# FlashMob.net
KiCad netlist of a schematic drawn in EAGLE
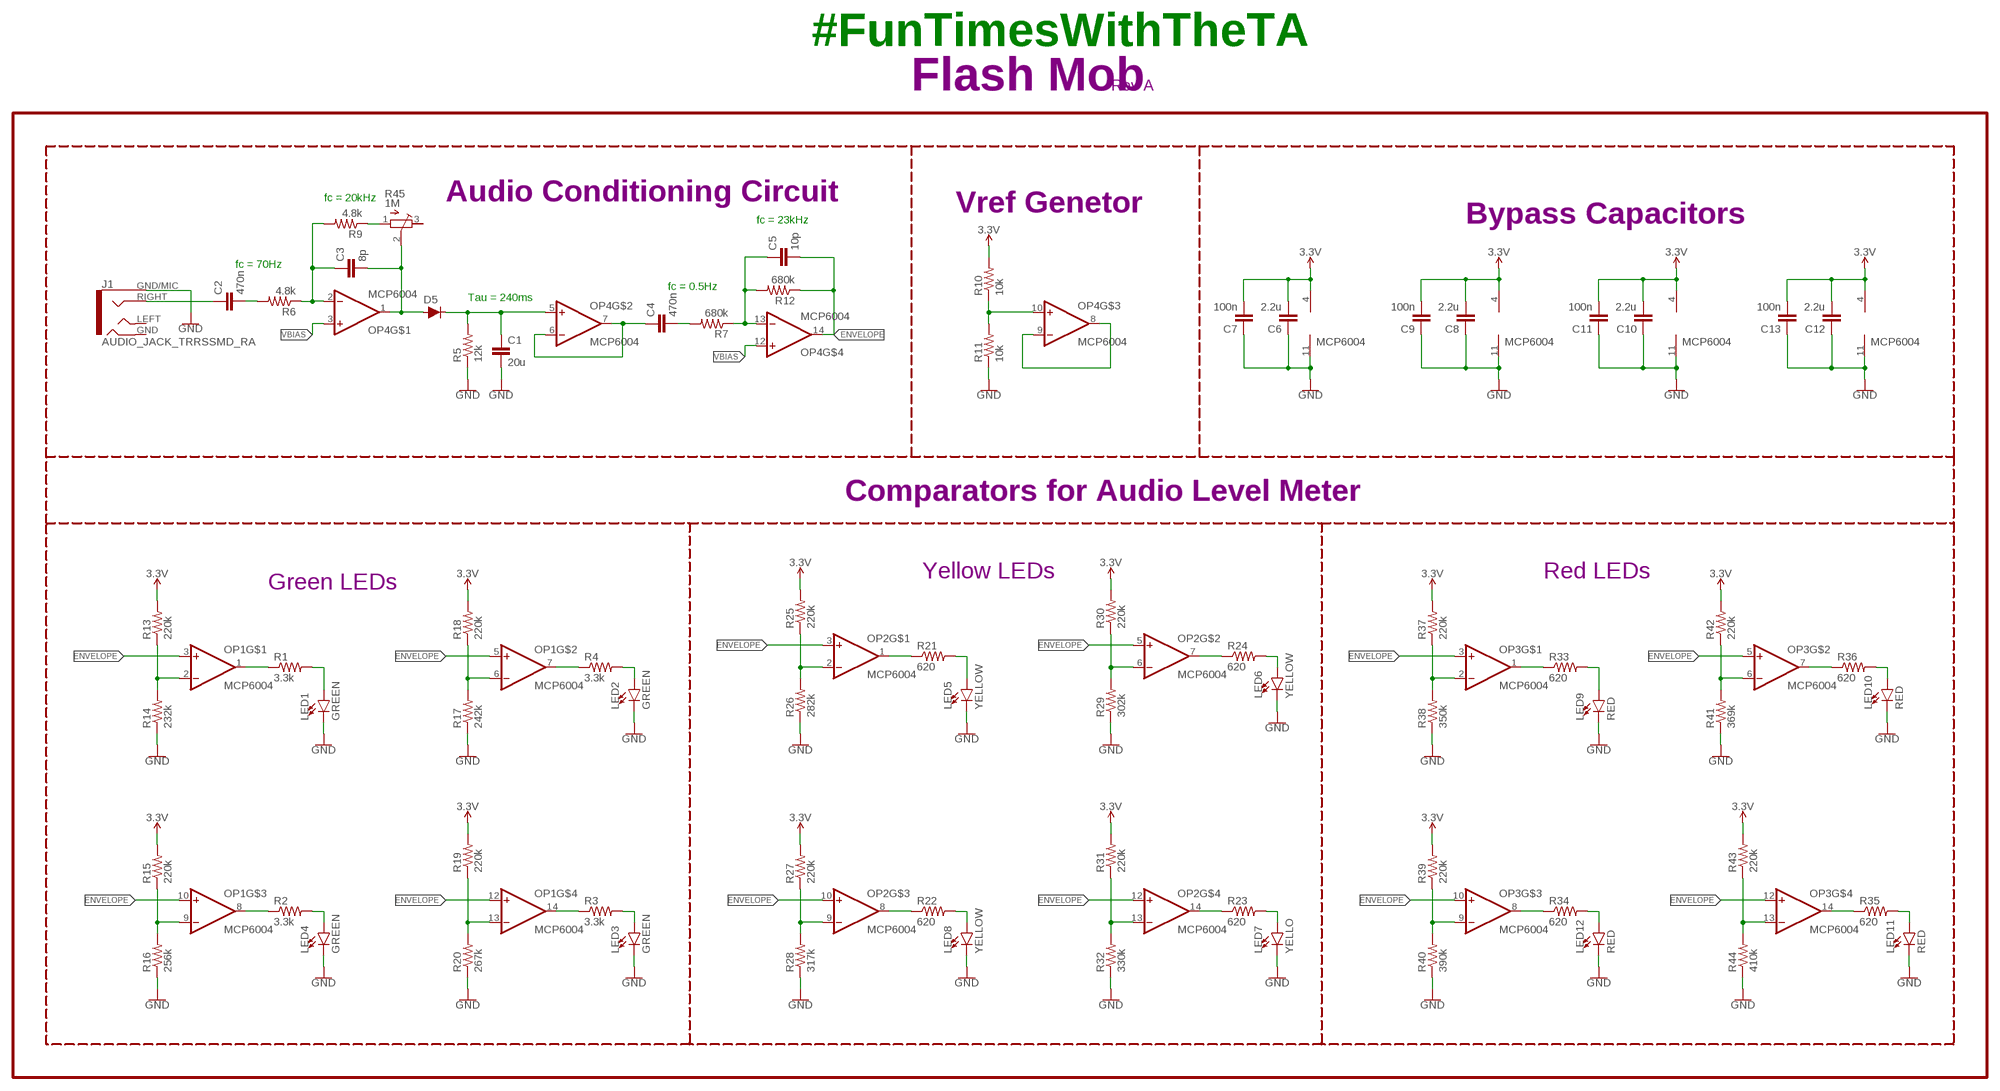
[diagram p0: schematic, sheet 1]

(export (version "E")
  (design (tool "Eeschema 10.0.6"))
  (components
    (comp (ref "C1")
      (value "20u")
      (footprint "eagle-import:C0402")
      (libsource (lib "eagle-import") (part "CAPACITOR0402"))
    )
    (comp (ref "C2")
      (value "470n")
      (footprint "eagle-import:C0402")
      (libsource (lib "eagle-import") (part "CAPACITOR0402"))
    )
    (comp (ref "C3")
      (value "8p")
      (footprint "eagle-import:C0402")
      (libsource (lib "eagle-import") (part "CAPACITOR0402"))
    )
    (comp (ref "C4")
      (value "470n")
      (footprint "eagle-import:C0402")
      (libsource (lib "eagle-import") (part "CAPACITOR0402"))
    )
    (comp (ref "C5")
      (value "10p")
      (footprint "eagle-import:C0402")
      (libsource (lib "eagle-import") (part "CAPACITOR0402"))
    )
    (comp (ref "C6")
      (value "2.2u")
      (footprint "eagle-import:C0402")
      (libsource (lib "eagle-import") (part "CAPACITOR0402"))
    )
    (comp (ref "C7")
      (value "100n")
      (footprint "eagle-import:C0402")
      (libsource (lib "eagle-import") (part "CAPACITOR0402"))
    )
    (comp (ref "C8")
      (value "2.2u")
      (footprint "eagle-import:C0402")
      (libsource (lib "eagle-import") (part "CAPACITOR0402"))
    )
    (comp (ref "C9")
      (value "100n")
      (footprint "eagle-import:C0402")
      (libsource (lib "eagle-import") (part "CAPACITOR0402"))
    )
    (comp (ref "C10")
      (value "2.2u")
      (footprint "eagle-import:C0402")
      (libsource (lib "eagle-import") (part "CAPACITOR0402"))
    )
    (comp (ref "C11")
      (value "100n")
      (footprint "eagle-import:C0402")
      (libsource (lib "eagle-import") (part "CAPACITOR0402"))
    )
    (comp (ref "C12")
      (value "2.2u")
      (footprint "eagle-import:C0402")
      (libsource (lib "eagle-import") (part "CAPACITOR0402"))
    )
    (comp (ref "C13")
      (value "100n")
      (footprint "eagle-import:C0402")
      (libsource (lib "eagle-import") (part "CAPACITOR0402"))
    )
    (comp (ref "D5")
      (value "DIODE-BAS16J")
      (footprint "eagle-import:SOD-323")
      (libsource (lib "eagle-import") (part "DIODE-BAS16J"))
    )
    (comp (ref "J1")
      (value "AUDIO_JACK_TRRSSMD_RA")
      (footprint "eagle-import:AUDIO_JACK_3.5MM_TRRS_SMD_RA")
      (libsource (lib "eagle-import") (part "AUDIO_JACK_TRRSSMD_RA"))
    )
    (comp (ref "LED1")
      (value "GREEN")
      (footprint "eagle-import:LED-0603")
      (libsource (lib "eagle-import") (part "LED0603"))
    )
    (comp (ref "LED2")
      (value "GREEN")
      (footprint "eagle-import:LED-0603")
      (libsource (lib "eagle-import") (part "LED0603"))
    )
    (comp (ref "LED3")
      (value "GREEN")
      (footprint "eagle-import:LED-0603")
      (libsource (lib "eagle-import") (part "LED0603"))
    )
    (comp (ref "LED4")
      (value "GREEN")
      (footprint "eagle-import:LED-0603")
      (libsource (lib "eagle-import") (part "LED0603"))
    )
    (comp (ref "LED5")
      (value "YELLOW")
      (footprint "eagle-import:LED-0603")
      (libsource (lib "eagle-import") (part "LED0603"))
    )
    (comp (ref "LED6")
      (value "YELLOW")
      (footprint "eagle-import:LED-0603")
      (libsource (lib "eagle-import") (part "LED0603"))
    )
    (comp (ref "LED7")
      (value "YELLO")
      (footprint "eagle-import:LED-0603")
      (libsource (lib "eagle-import") (part "LED0603"))
    )
    (comp (ref "LED8")
      (value "YELLOW")
      (footprint "eagle-import:LED-0603")
      (libsource (lib "eagle-import") (part "LED0603"))
    )
    (comp (ref "LED9")
      (value "RED")
      (footprint "eagle-import:LED-0603")
      (libsource (lib "eagle-import") (part "LED0603"))
    )
    (comp (ref "LED10")
      (value "RED")
      (footprint "eagle-import:LED-0603")
      (libsource (lib "eagle-import") (part "LED0603"))
    )
    (comp (ref "LED11")
      (value "RED")
      (footprint "eagle-import:LED-0603")
      (libsource (lib "eagle-import") (part "LED0603"))
    )
    (comp (ref "LED12")
      (value "RED")
      (footprint "eagle-import:LED-0603")
      (libsource (lib "eagle-import") (part "LED0603"))
    )
    (comp (ref "OP1")
      (value "MCP6004")
      (footprint "eagle-import:TSSOP14")
      (libsource (lib "eagle-import") (part "OP-QUAD-TSSOP14"))
    )
    (comp (ref "OP2")
      (value "MCP6004")
      (footprint "eagle-import:TSSOP14")
      (libsource (lib "eagle-import") (part "OP-QUAD-TSSOP14"))
    )
    (comp (ref "OP3")
      (value "MCP6004")
      (footprint "eagle-import:TSSOP14")
      (libsource (lib "eagle-import") (part "OP-QUAD-TSSOP14"))
    )
    (comp (ref "OP4")
      (value "MCP6004")
      (footprint "eagle-import:TSSOP14")
      (libsource (lib "eagle-import") (part "OP-QUAD-TSSOP14"))
    )
    (comp (ref "R1")
      (value "3.3k")
      (footprint "eagle-import:R0402")
      (libsource (lib "eagle-import") (part "RESISTOR0402"))
    )
    (comp (ref "R2")
      (value "3.3k")
      (footprint "eagle-import:R0402")
      (libsource (lib "eagle-import") (part "RESISTOR0402"))
    )
    (comp (ref "R3")
      (value "3.3k")
      (footprint "eagle-import:R0402")
      (libsource (lib "eagle-import") (part "RESISTOR0402"))
    )
    (comp (ref "R4")
      (value "3.3k")
      (footprint "eagle-import:R0402")
      (libsource (lib "eagle-import") (part "RESISTOR0402"))
    )
    (comp (ref "R5")
      (value "12k")
      (footprint "eagle-import:R0402")
      (libsource (lib "eagle-import") (part "RESISTOR0402"))
    )
    (comp (ref "R6")
      (value "4.8k")
      (footprint "eagle-import:R0402")
      (libsource (lib "eagle-import") (part "RESISTOR0402"))
    )
    (comp (ref "R7")
      (value "680k")
      (footprint "eagle-import:R0402")
      (libsource (lib "eagle-import") (part "RESISTOR0402"))
    )
    (comp (ref "R9")
      (value "4.8k")
      (footprint "eagle-import:R0402")
      (libsource (lib "eagle-import") (part "RESISTOR0402"))
    )
    (comp (ref "R10")
      (value "10k")
      (footprint "eagle-import:R0402")
      (libsource (lib "eagle-import") (part "RESISTOR0402"))
    )
    (comp (ref "R11")
      (value "10k")
      (footprint "eagle-import:R0402")
      (libsource (lib "eagle-import") (part "RESISTOR0402"))
    )
    (comp (ref "R12")
      (value "680k")
      (footprint "eagle-import:R0402")
      (libsource (lib "eagle-import") (part "RESISTOR0402"))
    )
    (comp (ref "R13")
      (value "220k")
      (footprint "eagle-import:R0402")
      (libsource (lib "eagle-import") (part "RESISTOR0402"))
    )
    (comp (ref "R14")
      (value "232k")
      (footprint "eagle-import:R0402")
      (libsource (lib "eagle-import") (part "RESISTOR0402"))
    )
    (comp (ref "R15")
      (value "220k")
      (footprint "eagle-import:R0402")
      (libsource (lib "eagle-import") (part "RESISTOR0402"))
    )
    (comp (ref "R16")
      (value "256k")
      (footprint "eagle-import:R0402")
      (libsource (lib "eagle-import") (part "RESISTOR0402"))
    )
    (comp (ref "R17")
      (value "242k")
      (footprint "eagle-import:R0402")
      (libsource (lib "eagle-import") (part "RESISTOR0402"))
    )
    (comp (ref "R18")
      (value "220k")
      (footprint "eagle-import:R0402")
      (libsource (lib "eagle-import") (part "RESISTOR0402"))
    )
    (comp (ref "R19")
      (value "220k")
      (footprint "eagle-import:R0402")
      (libsource (lib "eagle-import") (part "RESISTOR0402"))
    )
    (comp (ref "R20")
      (value "267k")
      (footprint "eagle-import:R0402")
      (libsource (lib "eagle-import") (part "RESISTOR0402"))
    )
    (comp (ref "R21")
      (value "620")
      (footprint "eagle-import:R0402")
      (libsource (lib "eagle-import") (part "RESISTOR0402"))
    )
    (comp (ref "R22")
      (value "620")
      (footprint "eagle-import:R0402")
      (libsource (lib "eagle-import") (part "RESISTOR0402"))
    )
    (comp (ref "R23")
      (value "620")
      (footprint "eagle-import:R0402")
      (libsource (lib "eagle-import") (part "RESISTOR0402"))
    )
    (comp (ref "R24")
      (value "620")
      (footprint "eagle-import:R0402")
      (libsource (lib "eagle-import") (part "RESISTOR0402"))
    )
    (comp (ref "R25")
      (value "220k")
      (footprint "eagle-import:R0402")
      (libsource (lib "eagle-import") (part "RESISTOR0402"))
    )
    (comp (ref "R26")
      (value "282k")
      (footprint "eagle-import:R0402")
      (libsource (lib "eagle-import") (part "RESISTOR0402"))
    )
    (comp (ref "R27")
      (value "220k")
      (footprint "eagle-import:R0402")
      (libsource (lib "eagle-import") (part "RESISTOR0402"))
    )
    (comp (ref "R28")
      (value "317k")
      (footprint "eagle-import:R0402")
      (libsource (lib "eagle-import") (part "RESISTOR0402"))
    )
    (comp (ref "R29")
      (value "302k")
      (footprint "eagle-import:R0402")
      (libsource (lib "eagle-import") (part "RESISTOR0402"))
    )
    (comp (ref "R30")
      (value "220k")
      (footprint "eagle-import:R0402")
      (libsource (lib "eagle-import") (part "RESISTOR0402"))
    )
    (comp (ref "R31")
      (value "220k")
      (footprint "eagle-import:R0402")
      (libsource (lib "eagle-import") (part "RESISTOR0402"))
    )
    (comp (ref "R32")
      (value "330k")
      (footprint "eagle-import:R0402")
      (libsource (lib "eagle-import") (part "RESISTOR0402"))
    )
    (comp (ref "R33")
      (value "620")
      (footprint "eagle-import:R0402")
      (libsource (lib "eagle-import") (part "RESISTOR0402"))
    )
    (comp (ref "R34")
      (value "620")
      (footprint "eagle-import:R0402")
      (libsource (lib "eagle-import") (part "RESISTOR0402"))
    )
    (comp (ref "R35")
      (value "620")
      (footprint "eagle-import:R0402")
      (libsource (lib "eagle-import") (part "RESISTOR0402"))
    )
    (comp (ref "R36")
      (value "620")
      (footprint "eagle-import:R0402")
      (libsource (lib "eagle-import") (part "RESISTOR0402"))
    )
    (comp (ref "R37")
      (value "220k")
      (footprint "eagle-import:R0402")
      (libsource (lib "eagle-import") (part "RESISTOR0402"))
    )
    (comp (ref "R38")
      (value "350k")
      (footprint "eagle-import:R0402")
      (libsource (lib "eagle-import") (part "RESISTOR0402"))
    )
    (comp (ref "R39")
      (value "220k")
      (footprint "eagle-import:R0402")
      (libsource (lib "eagle-import") (part "RESISTOR0402"))
    )
    (comp (ref "R40")
      (value "390k")
      (footprint "eagle-import:R0402")
      (libsource (lib "eagle-import") (part "RESISTOR0402"))
    )
    (comp (ref "R41")
      (value "369k")
      (footprint "eagle-import:R0402")
      (libsource (lib "eagle-import") (part "RESISTOR0402"))
    )
    (comp (ref "R42")
      (value "220k")
      (footprint "eagle-import:R0402")
      (libsource (lib "eagle-import") (part "RESISTOR0402"))
    )
    (comp (ref "R43")
      (value "220k")
      (footprint "eagle-import:R0402")
      (libsource (lib "eagle-import") (part "RESISTOR0402"))
    )
    (comp (ref "R44")
      (value "410k")
      (footprint "eagle-import:R0402")
      (libsource (lib "eagle-import") (part "RESISTOR0402"))
    )
    (comp (ref "R45")
      (value "1M")
      (footprint "eagle-import:16MMROTARYPOT")
      (libsource (lib "eagle-import") (part "TRIM-POT-P160"))
    )
    (comp (ref "U$1")
      (value "REVISION.A")
      (footprint "eagle-import:REV.A")
      (libsource (lib "eagle-import") (part "REVISION.A"))
    )
  )
  (nets
    (net (code "1") (name "3.3V") (class "Default")
      (node (ref "C10") (pin "2") (pinfunction "2_2") (pintype "passive"))
      (node (ref "C11") (pin "2") (pinfunction "2_2") (pintype "passive"))
      (node (ref "C12") (pin "2") (pinfunction "2_2") (pintype "passive"))
      (node (ref "C13") (pin "2") (pinfunction "2_2") (pintype "passive"))
      (node (ref "C6") (pin "2") (pinfunction "2_2") (pintype "passive"))
      (node (ref "C7") (pin "2") (pinfunction "2_2") (pintype "passive"))
      (node (ref "C8") (pin "2") (pinfunction "2_2") (pintype "passive"))
      (node (ref "C9") (pin "2") (pinfunction "2_2") (pintype "passive"))
      (node (ref "OP1") (pin "4") (pinfunction "V+_4") (pintype "power_in"))
      (node (ref "OP2") (pin "4") (pinfunction "V+_4") (pintype "power_in"))
      (node (ref "OP3") (pin "4") (pinfunction "V+_4") (pintype "power_in"))
      (node (ref "OP4") (pin "4") (pinfunction "V+_4") (pintype "power_in"))
      (node (ref "R10") (pin "2") (pinfunction "2_2") (pintype "passive"))
      (node (ref "R13") (pin "2") (pinfunction "2_2") (pintype "passive"))
      (node (ref "R15") (pin "2") (pinfunction "2_2") (pintype "passive"))
      (node (ref "R18") (pin "2") (pinfunction "2_2") (pintype "passive"))
      (node (ref "R19") (pin "2") (pinfunction "2_2") (pintype "passive"))
      (node (ref "R25") (pin "2") (pinfunction "2_2") (pintype "passive"))
      (node (ref "R27") (pin "2") (pinfunction "2_2") (pintype "passive"))
      (node (ref "R30") (pin "2") (pinfunction "2_2") (pintype "passive"))
      (node (ref "R31") (pin "2") (pinfunction "2_2") (pintype "passive"))
      (node (ref "R37") (pin "2") (pinfunction "2_2") (pintype "passive"))
      (node (ref "R39") (pin "2") (pinfunction "2_2") (pintype "passive"))
      (node (ref "R42") (pin "2") (pinfunction "2_2") (pintype "passive"))
      (node (ref "R43") (pin "2") (pinfunction "2_2") (pintype "passive"))
    )
    (net (code "2") (name "ENVELOPE") (class "Default")
      (node (ref "C5") (pin "2") (pinfunction "2_2") (pintype "passive"))
      (node (ref "OP1") (pin "10") (pinfunction "+IN_10") (pintype "input"))
      (node (ref "OP1") (pin "12") (pinfunction "+IN_12") (pintype "input"))
      (node (ref "OP1") (pin "3") (pinfunction "+IN_3") (pintype "input"))
      (node (ref "OP1") (pin "5") (pinfunction "+IN_5") (pintype "input"))
      (node (ref "OP2") (pin "10") (pinfunction "+IN_10") (pintype "input"))
      (node (ref "OP2") (pin "12") (pinfunction "+IN_12") (pintype "input"))
      (node (ref "OP2") (pin "3") (pinfunction "+IN_3") (pintype "input"))
      (node (ref "OP2") (pin "5") (pinfunction "+IN_5") (pintype "input"))
      (node (ref "OP3") (pin "10") (pinfunction "+IN_10") (pintype "input"))
      (node (ref "OP3") (pin "12") (pinfunction "+IN_12") (pintype "input"))
      (node (ref "OP3") (pin "3") (pinfunction "+IN_3") (pintype "input"))
      (node (ref "OP3") (pin "5") (pinfunction "+IN_5") (pintype "input"))
      (node (ref "OP4") (pin "14") (pinfunction "OUT_14") (pintype "output"))
      (node (ref "R12") (pin "1") (pinfunction "1_1") (pintype "passive"))
    )
    (net (code "3") (name "GND") (class "Default")
      (node (ref "C1") (pin "2") (pinfunction "2_2") (pintype "passive"))
      (node (ref "C10") (pin "1") (pinfunction "1_1") (pintype "passive"))
      (node (ref "C11") (pin "1") (pinfunction "1_1") (pintype "passive"))
      (node (ref "C12") (pin "1") (pinfunction "1_1") (pintype "passive"))
      (node (ref "C13") (pin "1") (pinfunction "1_1") (pintype "passive"))
      (node (ref "C6") (pin "1") (pinfunction "1_1") (pintype "passive"))
      (node (ref "C7") (pin "1") (pinfunction "1_1") (pintype "passive"))
      (node (ref "C8") (pin "1") (pinfunction "1_1") (pintype "passive"))
      (node (ref "C9") (pin "1") (pinfunction "1_1") (pintype "passive"))
      (node (ref "J1") (pin "GND/MIC") (pinfunction "SLEEVE_GND/MIC") (pintype "bidirectional"))
      (node (ref "LED1") (pin "C") (pinfunction "C_C") (pintype "passive"))
      (node (ref "LED10") (pin "C") (pinfunction "C_C") (pintype "passive"))
      (node (ref "LED11") (pin "C") (pinfunction "C_C") (pintype "passive"))
      (node (ref "LED12") (pin "C") (pinfunction "C_C") (pintype "passive"))
      (node (ref "LED2") (pin "C") (pinfunction "C_C") (pintype "passive"))
      (node (ref "LED3") (pin "C") (pinfunction "C_C") (pintype "passive"))
      (node (ref "LED4") (pin "C") (pinfunction "C_C") (pintype "passive"))
      (node (ref "LED5") (pin "C") (pinfunction "C_C") (pintype "passive"))
      (node (ref "LED6") (pin "C") (pinfunction "C_C") (pintype "passive"))
      (node (ref "LED7") (pin "C") (pinfunction "C_C") (pintype "passive"))
      (node (ref "LED8") (pin "C") (pinfunction "C_C") (pintype "passive"))
      (node (ref "LED9") (pin "C") (pinfunction "C_C") (pintype "passive"))
      (node (ref "OP1") (pin "11") (pinfunction "V-_11") (pintype "power_in"))
      (node (ref "OP2") (pin "11") (pinfunction "V-_11") (pintype "power_in"))
      (node (ref "OP3") (pin "11") (pinfunction "V-_11") (pintype "power_in"))
      (node (ref "OP4") (pin "11") (pinfunction "V-_11") (pintype "power_in"))
      (node (ref "R11") (pin "1") (pinfunction "1_1") (pintype "passive"))
      (node (ref "R14") (pin "1") (pinfunction "1_1") (pintype "passive"))
      (node (ref "R16") (pin "1") (pinfunction "1_1") (pintype "passive"))
      (node (ref "R17") (pin "1") (pinfunction "1_1") (pintype "passive"))
      (node (ref "R20") (pin "1") (pinfunction "1_1") (pintype "passive"))
      (node (ref "R26") (pin "1") (pinfunction "1_1") (pintype "passive"))
      (node (ref "R28") (pin "1") (pinfunction "1_1") (pintype "passive"))
      (node (ref "R29") (pin "1") (pinfunction "1_1") (pintype "passive"))
      (node (ref "R32") (pin "1") (pinfunction "1_1") (pintype "passive"))
      (node (ref "R38") (pin "1") (pinfunction "1_1") (pintype "passive"))
      (node (ref "R40") (pin "1") (pinfunction "1_1") (pintype "passive"))
      (node (ref "R41") (pin "1") (pinfunction "1_1") (pintype "passive"))
      (node (ref "R44") (pin "1") (pinfunction "1_1") (pintype "passive"))
      (node (ref "R5") (pin "1") (pinfunction "1_1") (pintype "passive"))
    )
    (net (code "4") (name "Net-(C2-Pad2)") (class "Default")
      (node (ref "C2") (pin "2") (pinfunction "2_2") (pintype "passive"))
      (node (ref "R6") (pin "2") (pinfunction "2_2") (pintype "passive"))
    )
    (net (code "5") (name "Net-(C4-Pad2)") (class "Default")
      (node (ref "C4") (pin "2") (pinfunction "2_2") (pintype "passive"))
      (node (ref "R7") (pin "2") (pinfunction "2_2") (pintype "passive"))
    )
    (net (code "6") (name "Net-(J1-RING1)") (class "Default")
      (node (ref "C2") (pin "1") (pinfunction "1_1") (pintype "passive"))
      (node (ref "J1") (pin "RIGHT") (pinfunction "RING1_RIGHT") (pintype "bidirectional"))
    )
    (net (code "7") (name "Net-(LED1-PadA)") (class "Default")
      (node (ref "LED1") (pin "A") (pinfunction "A_A") (pintype "passive"))
      (node (ref "R1") (pin "2") (pinfunction "2_2") (pintype "passive"))
    )
    (net (code "8") (name "Net-(LED2-PadA)") (class "Default")
      (node (ref "LED2") (pin "A") (pinfunction "A_A") (pintype "passive"))
      (node (ref "R4") (pin "2") (pinfunction "2_2") (pintype "passive"))
    )
    (net (code "9") (name "Net-(LED3-PadA)") (class "Default")
      (node (ref "LED3") (pin "A") (pinfunction "A_A") (pintype "passive"))
      (node (ref "R3") (pin "2") (pinfunction "2_2") (pintype "passive"))
    )
    (net (code "10") (name "Net-(LED4-PadA)") (class "Default")
      (node (ref "LED4") (pin "A") (pinfunction "A_A") (pintype "passive"))
      (node (ref "R2") (pin "2") (pinfunction "2_2") (pintype "passive"))
    )
    (net (code "11") (name "Net-(LED5-PadA)") (class "Default")
      (node (ref "LED5") (pin "A") (pinfunction "A_A") (pintype "passive"))
      (node (ref "R21") (pin "2") (pinfunction "2_2") (pintype "passive"))
    )
    (net (code "12") (name "Net-(LED6-PadA)") (class "Default")
      (node (ref "LED6") (pin "A") (pinfunction "A_A") (pintype "passive"))
      (node (ref "R24") (pin "2") (pinfunction "2_2") (pintype "passive"))
    )
    (net (code "13") (name "Net-(LED7-PadA)") (class "Default")
      (node (ref "LED7") (pin "A") (pinfunction "A_A") (pintype "passive"))
      (node (ref "R23") (pin "2") (pinfunction "2_2") (pintype "passive"))
    )
    (net (code "14") (name "Net-(LED8-PadA)") (class "Default")
      (node (ref "LED8") (pin "A") (pinfunction "A_A") (pintype "passive"))
      (node (ref "R22") (pin "2") (pinfunction "2_2") (pintype "passive"))
    )
    (net (code "15") (name "Net-(LED9-PadA)") (class "Default")
      (node (ref "LED9") (pin "A") (pinfunction "A_A") (pintype "passive"))
      (node (ref "R33") (pin "2") (pinfunction "2_2") (pintype "passive"))
    )
    (net (code "16") (name "Net-(LED10-PadA)") (class "Default")
      (node (ref "LED10") (pin "A") (pinfunction "A_A") (pintype "passive"))
      (node (ref "R36") (pin "2") (pinfunction "2_2") (pintype "passive"))
    )
    (net (code "17") (name "Net-(LED11-PadA)") (class "Default")
      (node (ref "LED11") (pin "A") (pinfunction "A_A") (pintype "passive"))
      (node (ref "R35") (pin "2") (pinfunction "2_2") (pintype "passive"))
    )
    (net (code "18") (name "Net-(LED12-PadA)") (class "Default")
      (node (ref "LED12") (pin "A") (pinfunction "A_A") (pintype "passive"))
      (node (ref "R34") (pin "2") (pinfunction "2_2") (pintype "passive"))
    )
    (net (code "19") (name "Net-(OP1A--IN)") (class "Default")
      (node (ref "OP1") (pin "2") (pinfunction "-IN_2") (pintype "input"))
      (node (ref "R13") (pin "1") (pinfunction "1_1") (pintype "passive"))
      (node (ref "R14") (pin "2") (pinfunction "2_2") (pintype "passive"))
    )
    (net (code "20") (name "Net-(OP1A-OUT)") (class "Default")
      (node (ref "OP1") (pin "1") (pinfunction "OUT_1") (pintype "output"))
      (node (ref "R1") (pin "1") (pinfunction "1_1") (pintype "passive"))
    )
    (net (code "21") (name "Net-(OP1B--IN)") (class "Default")
      (node (ref "OP1") (pin "6") (pinfunction "-IN_6") (pintype "input"))
      (node (ref "R17") (pin "2") (pinfunction "2_2") (pintype "passive"))
      (node (ref "R18") (pin "1") (pinfunction "1_1") (pintype "passive"))
    )
    (net (code "22") (name "Net-(OP1B-OUT)") (class "Default")
      (node (ref "OP1") (pin "7") (pinfunction "OUT_7") (pintype "output"))
      (node (ref "R4") (pin "1") (pinfunction "1_1") (pintype "passive"))
    )
    (net (code "23") (name "Net-(OP1C--IN)") (class "Default")
      (node (ref "OP1") (pin "9") (pinfunction "-IN_9") (pintype "input"))
      (node (ref "R15") (pin "1") (pinfunction "1_1") (pintype "passive"))
      (node (ref "R16") (pin "2") (pinfunction "2_2") (pintype "passive"))
    )
    (net (code "24") (name "Net-(OP1C-OUT)") (class "Default")
      (node (ref "OP1") (pin "8") (pinfunction "OUT_8") (pintype "output"))
      (node (ref "R2") (pin "1") (pinfunction "1_1") (pintype "passive"))
    )
    (net (code "25") (name "Net-(OP1D--IN)") (class "Default")
      (node (ref "OP1") (pin "13") (pinfunction "-IN_13") (pintype "input"))
      (node (ref "R19") (pin "1") (pinfunction "1_1") (pintype "passive"))
      (node (ref "R20") (pin "2") (pinfunction "2_2") (pintype "passive"))
    )
    (net (code "26") (name "Net-(OP1D-OUT)") (class "Default")
      (node (ref "OP1") (pin "14") (pinfunction "OUT_14") (pintype "output"))
      (node (ref "R3") (pin "1") (pinfunction "1_1") (pintype "passive"))
    )
    (net (code "27") (name "Net-(OP2A--IN)") (class "Default")
      (node (ref "OP2") (pin "2") (pinfunction "-IN_2") (pintype "input"))
      (node (ref "R25") (pin "1") (pinfunction "1_1") (pintype "passive"))
      (node (ref "R26") (pin "2") (pinfunction "2_2") (pintype "passive"))
    )
    (net (code "28") (name "Net-(OP2A-OUT)") (class "Default")
      (node (ref "OP2") (pin "1") (pinfunction "OUT_1") (pintype "output"))
      (node (ref "R21") (pin "1") (pinfunction "1_1") (pintype "passive"))
    )
    (net (code "29") (name "Net-(OP2B--IN)") (class "Default")
      (node (ref "OP2") (pin "6") (pinfunction "-IN_6") (pintype "input"))
      (node (ref "R29") (pin "2") (pinfunction "2_2") (pintype "passive"))
      (node (ref "R30") (pin "1") (pinfunction "1_1") (pintype "passive"))
    )
    (net (code "30") (name "Net-(OP2B-OUT)") (class "Default")
      (node (ref "OP2") (pin "7") (pinfunction "OUT_7") (pintype "output"))
      (node (ref "R24") (pin "1") (pinfunction "1_1") (pintype "passive"))
    )
    (net (code "31") (name "Net-(OP2C--IN)") (class "Default")
      (node (ref "OP2") (pin "9") (pinfunction "-IN_9") (pintype "input"))
      (node (ref "R27") (pin "1") (pinfunction "1_1") (pintype "passive"))
      (node (ref "R28") (pin "2") (pinfunction "2_2") (pintype "passive"))
    )
    (net (code "32") (name "Net-(OP2C-OUT)") (class "Default")
      (node (ref "OP2") (pin "8") (pinfunction "OUT_8") (pintype "output"))
      (node (ref "R22") (pin "1") (pinfunction "1_1") (pintype "passive"))
    )
    (net (code "33") (name "Net-(OP2D--IN)") (class "Default")
      (node (ref "OP2") (pin "13") (pinfunction "-IN_13") (pintype "input"))
      (node (ref "R31") (pin "1") (pinfunction "1_1") (pintype "passive"))
      (node (ref "R32") (pin "2") (pinfunction "2_2") (pintype "passive"))
    )
    (net (code "34") (name "Net-(OP2D-OUT)") (class "Default")
      (node (ref "OP2") (pin "14") (pinfunction "OUT_14") (pintype "output"))
      (node (ref "R23") (pin "1") (pinfunction "1_1") (pintype "passive"))
    )
    (net (code "35") (name "Net-(OP3A--IN)") (class "Default")
      (node (ref "OP3") (pin "2") (pinfunction "-IN_2") (pintype "input"))
      (node (ref "R37") (pin "1") (pinfunction "1_1") (pintype "passive"))
      (node (ref "R38") (pin "2") (pinfunction "2_2") (pintype "passive"))
    )
    (net (code "36") (name "Net-(OP3A-OUT)") (class "Default")
      (node (ref "OP3") (pin "1") (pinfunction "OUT_1") (pintype "output"))
      (node (ref "R33") (pin "1") (pinfunction "1_1") (pintype "passive"))
    )
    (net (code "37") (name "Net-(OP3B--IN)") (class "Default")
      (node (ref "OP3") (pin "6") (pinfunction "-IN_6") (pintype "input"))
      (node (ref "R41") (pin "2") (pinfunction "2_2") (pintype "passive"))
      (node (ref "R42") (pin "1") (pinfunction "1_1") (pintype "passive"))
    )
    (net (code "38") (name "Net-(OP3B-OUT)") (class "Default")
      (node (ref "OP3") (pin "7") (pinfunction "OUT_7") (pintype "output"))
      (node (ref "R36") (pin "1") (pinfunction "1_1") (pintype "passive"))
    )
    (net (code "39") (name "Net-(OP3C--IN)") (class "Default")
      (node (ref "OP3") (pin "9") (pinfunction "-IN_9") (pintype "input"))
      (node (ref "R39") (pin "1") (pinfunction "1_1") (pintype "passive"))
      (node (ref "R40") (pin "2") (pinfunction "2_2") (pintype "passive"))
    )
    (net (code "40") (name "Net-(OP3C-OUT)") (class "Default")
      (node (ref "OP3") (pin "8") (pinfunction "OUT_8") (pintype "output"))
      (node (ref "R34") (pin "1") (pinfunction "1_1") (pintype "passive"))
    )
    (net (code "41") (name "Net-(OP3D--IN)") (class "Default")
      (node (ref "OP3") (pin "13") (pinfunction "-IN_13") (pintype "input"))
      (node (ref "R43") (pin "1") (pinfunction "1_1") (pintype "passive"))
      (node (ref "R44") (pin "2") (pinfunction "2_2") (pintype "passive"))
    )
    (net (code "42") (name "Net-(OP3D-OUT)") (class "Default")
      (node (ref "OP3") (pin "14") (pinfunction "OUT_14") (pintype "output"))
      (node (ref "R35") (pin "1") (pinfunction "1_1") (pintype "passive"))
    )
    (net (code "43") (name "Net-(OP4A--IN)") (class "Default")
      (node (ref "C3") (pin "1") (pinfunction "1_1") (pintype "passive"))
      (node (ref "OP4") (pin "2") (pinfunction "-IN_2") (pintype "input"))
      (node (ref "R6") (pin "1") (pinfunction "1_1") (pintype "passive"))
      (node (ref "R9") (pin "2") (pinfunction "2_2") (pintype "passive"))
    )
    (net (code "44") (name "Net-(OP4A-OUT)") (class "Default")
      (node (ref "C3") (pin "2") (pinfunction "2_2") (pintype "passive"))
      (node (ref "D5") (pin "A") (pinfunction "A_A") (pintype "passive"))
      (node (ref "OP4") (pin "1") (pinfunction "OUT_1") (pintype "output"))
      (node (ref "R45") (pin "2") (pinfunction "S_2") (pintype "passive"))
    )
    (net (code "45") (name "Net-(OP4B-+IN)") (class "Default")
      (node (ref "C1") (pin "1") (pinfunction "1_1") (pintype "passive"))
      (node (ref "D5") (pin "C") (pinfunction "C_C") (pintype "passive"))
      (node (ref "OP4") (pin "5") (pinfunction "+IN_5") (pintype "input"))
      (node (ref "R5") (pin "2") (pinfunction "2_2") (pintype "passive"))
    )
    (net (code "46") (name "Net-(OP4B--IN)") (class "Default")
      (node (ref "C4") (pin "1") (pinfunction "1_1") (pintype "passive"))
      (node (ref "OP4") (pin "6") (pinfunction "-IN_6") (pintype "input"))
      (node (ref "OP4") (pin "7") (pinfunction "OUT_7") (pintype "output"))
    )
    (net (code "47") (name "Net-(OP4C-+IN)") (class "Default")
      (node (ref "OP4") (pin "10") (pinfunction "+IN_10") (pintype "input"))
      (node (ref "R10") (pin "1") (pinfunction "1_1") (pintype "passive"))
      (node (ref "R11") (pin "2") (pinfunction "2_2") (pintype "passive"))
    )
    (net (code "48") (name "Net-(OP4C--IN)") (class "Default")
      (node (ref "OP4") (pin "8") (pinfunction "OUT_8") (pintype "output"))
      (node (ref "OP4") (pin "9") (pinfunction "-IN_9") (pintype "input"))
    )
    (net (code "49") (name "Net-(OP4D--IN)") (class "Default")
      (node (ref "C5") (pin "1") (pinfunction "1_1") (pintype "passive"))
      (node (ref "OP4") (pin "13") (pinfunction "-IN_13") (pintype "input"))
      (node (ref "R12") (pin "2") (pinfunction "2_2") (pintype "passive"))
      (node (ref "R7") (pin "1") (pinfunction "1_1") (pintype "passive"))
    )
    (net (code "50") (name "Net-(R45-A)") (class "Default")
      (node (ref "R45") (pin "1") (pinfunction "A_1") (pintype "passive"))
      (node (ref "R9") (pin "1") (pinfunction "1_1") (pintype "passive"))
    )
    (net (code "51") (name "VBIAS") (class "Default")
      (node (ref "OP4") (pin "12") (pinfunction "+IN_12") (pintype "input"))
      (node (ref "OP4") (pin "3") (pinfunction "+IN_3") (pintype "input"))
    )
    (net (code "52") (name "unconnected-(J1-RING2-PadGND)") (class "Default")
      (node (ref "J1") (pin "GND") (pinfunction "RING2_GND") (pintype "bidirectional"))
    )
    (net (code "53") (name "unconnected-(J1-TIP-PadLEFT)") (class "Default")
      (node (ref "J1") (pin "LEFT") (pinfunction "TIP_LEFT") (pintype "bidirectional"))
    )
    (net (code "54") (name "unconnected-(R45-E-Pad3)") (class "Default")
      (node (ref "R45") (pin "3") (pinfunction "E_3") (pintype "passive"))
    )
  )
)
